# Mosfets.net
KiCad netlist of a schematic drawn in Altium Designer
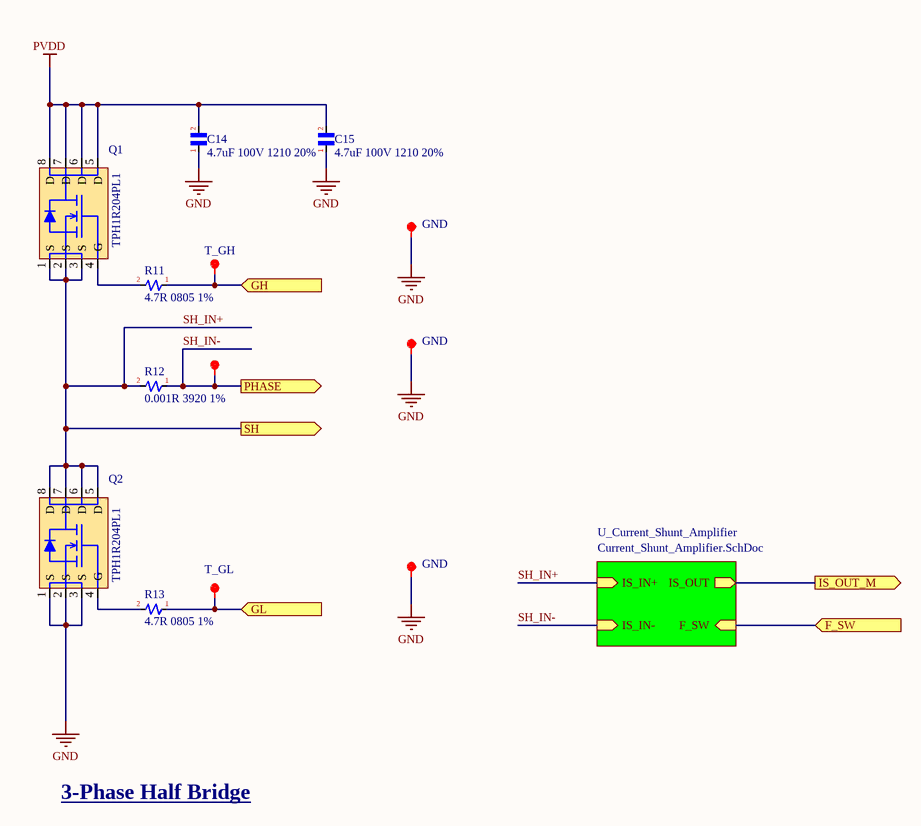
[diagram p0: Mosfets.SchDoc]

(export (version "E")
  (design (tool "Eeschema 10.0.6"))
  (components
    (comp (ref "C14")
      (value "4.7uF 100V 1210 20%")
      (footprint "C_1210")
      (description "CAP  0603 20%")
      (libsource (lib "Walton_EED") (part "Capacitor{gt}{gt} Non-Polar"))
    )
    (comp (ref "C15")
      (value "4.7uF 100V 1210 20%")
      (footprint "C_1210")
      (description "CAP  0603 20%")
      (libsource (lib "Walton_EED") (part "Capacitor{gt}{gt} Non-Polar"))
    )
    (comp (ref "Q1")
      (value "TPH1R204PL1")
      (footprint "TRANS_STL60P4LLF6")
      (description "N-channel 60 V, 3 mOhm typ., 130 A STripFET F7 Power MOSFET in a PowerFLAT 5x6 package")
      (libsource (lib "Walton_EED_13_05_2024") (part "MOSFET_N{gt}{gt}ST130N6F7"))
    )
    (comp (ref "Q2")
      (value "TPH1R204PL1")
      (footprint "TRANS_STL60P4LLF6")
      (description "N-channel 60 V, 3 mOhm typ., 130 A STripFET F7 Power MOSFET in a PowerFLAT 5x6 package")
      (libsource (lib "Walton_EED_13_05_2024") (part "MOSFET_N{gt}{gt}ST130N6F7"))
    )
    (comp (ref "R11")
      (value "4.7R 0805 1%")
      (footprint "R_0805")
      (description "RES 0603 20%")
      (libsource (lib "Walton_EED") (part "Resistor{gt}{gt} General Purpose"))
    )
    (comp (ref "R12")
      (value "0.001R 3920 1%")
      (footprint "R_3920")
      (description "RES 0603 20%")
      (libsource (lib "Walton_EED") (part "Resistor{gt}{gt} General Purpose"))
    )
    (comp (ref "R13")
      (value "4.7R 0805 1%")
      (footprint "R_0805")
      (description "RES 0603 20%")
      (libsource (lib "Walton_EED") (part "Resistor{gt}{gt} General Purpose"))
    )
    (comp (ref "TP22") (value "T_GH") (footprint "TP_1mm_SMD") (libsource (lib "*") (part "Test point TP")))
    (comp (ref "TP25") (value "GND") (footprint "TP_1mm_SMD") (libsource (lib "*") (part "Test point TP")))
    (comp (ref "TP28") (value "GND") (footprint "TP_1mm_SMD") (libsource (lib "*") (part "Test point TP")))
    (comp (ref "TP31") (value "~") (footprint "TP_1mm_SMD") (libsource (lib "*") (part "Test point TP")))
    (comp (ref "TP34") (value "T_GL") (footprint "TP_1mm_SMD") (libsource (lib "*") (part "Test point TP")))
    (comp (ref "TP37") (value "GND") (footprint "TP_1mm_SMD") (libsource (lib "*") (part "Test point TP")))
  )
  (nets
    (net (code "3") (name "/GH") (class "Default")
      (node (ref "R11") (pin "1") (pinfunction "1_1") (pintype "passive"))
      (node (ref "TP22") (pin "1") (pinfunction "1_1") (pintype "passive"))
    )
    (net (code "4") (name "/GL") (class "Default")
      (node (ref "R13") (pin "1") (pinfunction "1_1") (pintype "passive"))
      (node (ref "TP34") (pin "1") (pinfunction "1_1") (pintype "passive"))
    )
    (net (code "5") (name "/SH_IN+") (class "Default")
      (node (ref "Q1") (pin "1") (pinfunction "S_1") (pintype "passive"))
      (node (ref "Q1") (pin "2") (pinfunction "S_2") (pintype "passive"))
      (node (ref "Q1") (pin "3") (pinfunction "S_3") (pintype "passive"))
      (node (ref "Q2") (pin "5") (pinfunction "D_5") (pintype "passive"))
      (node (ref "Q2") (pin "6") (pinfunction "D_6") (pintype "passive"))
      (node (ref "Q2") (pin "7") (pinfunction "D_7") (pintype "passive"))
      (node (ref "Q2") (pin "8") (pinfunction "D_8") (pintype "passive"))
      (node (ref "R12") (pin "2") (pinfunction "2_2") (pintype "passive"))
    )
    (net (code "6") (name "/SH_IN-") (class "Default")
      (node (ref "R12") (pin "1") (pinfunction "1_1") (pintype "passive"))
      (node (ref "TP31") (pin "1") (pinfunction "1_1") (pintype "passive"))
    )
    (net (code "7") (name "GND") (class "Default")
      (node (ref "C14") (pin "1") (pinfunction "1_1") (pintype "passive"))
      (node (ref "C15") (pin "1") (pinfunction "1_1") (pintype "passive"))
      (node (ref "Q2") (pin "1") (pinfunction "S_1") (pintype "passive"))
      (node (ref "Q2") (pin "2") (pinfunction "S_2") (pintype "passive"))
      (node (ref "Q2") (pin "3") (pinfunction "S_3") (pintype "passive"))
      (node (ref "TP25") (pin "1") (pinfunction "1_1") (pintype "passive"))
      (node (ref "TP28") (pin "1") (pinfunction "1_1") (pintype "passive"))
      (node (ref "TP37") (pin "1") (pinfunction "1_1") (pintype "passive"))
    )
    (net (code "8") (name "Net-(Q1-G)") (class "Default")
      (node (ref "Q1") (pin "4") (pinfunction "G_4") (pintype "passive"))
      (node (ref "R11") (pin "2") (pinfunction "2_2") (pintype "passive"))
    )
    (net (code "9") (name "Net-(Q2-G)") (class "Default")
      (node (ref "Q2") (pin "4") (pinfunction "G_4") (pintype "passive"))
      (node (ref "R13") (pin "2") (pinfunction "2_2") (pintype "passive"))
    )
    (net (code "10") (name "PVDD") (class "Default")
      (node (ref "C14") (pin "2") (pinfunction "2_2") (pintype "passive"))
      (node (ref "C15") (pin "2") (pinfunction "2_2") (pintype "passive"))
      (node (ref "Q1") (pin "5") (pinfunction "D_5") (pintype "passive"))
      (node (ref "Q1") (pin "6") (pinfunction "D_6") (pintype "passive"))
      (node (ref "Q1") (pin "7") (pinfunction "D_7") (pintype "passive"))
      (node (ref "Q1") (pin "8") (pinfunction "D_8") (pintype "passive"))
    )
  )
)
